# GateDriver.net
KiCad netlist of a schematic drawn in Altium Designer
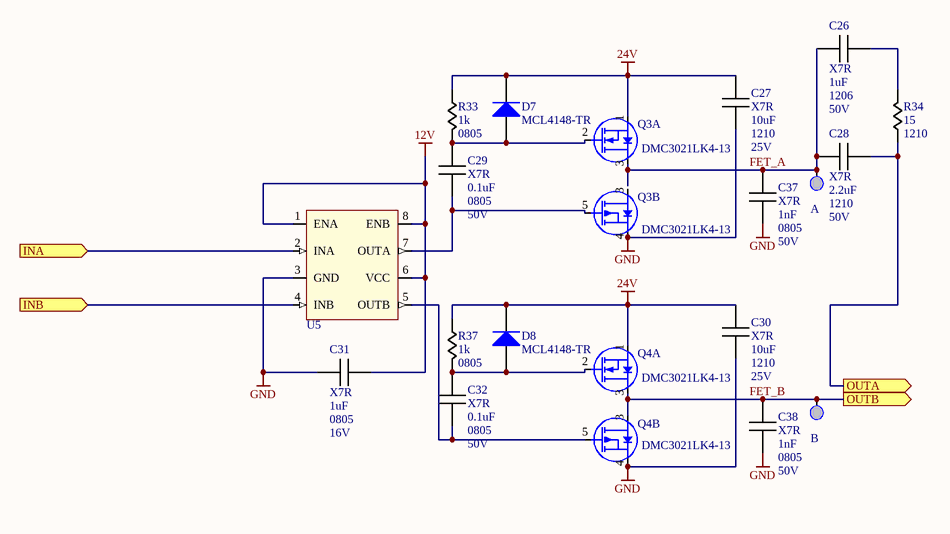
[diagram p0: GateDriver.SchDoc]

(export (version "E")
  (design (tool "Eeschema 10.0.6"))
  (components
    (comp (ref "A")
      (value "Testpoint")
      (footprint "Keystone5002")
      (fields (field (name "DIGIKEY PART") "36-5002-ND") (field (name "MOUSER PART") "534-5002"))
      (libsource (lib "UD2 CPLD") (part "Testpoint"))
    )
    (comp (ref "B")
      (value "Testpoint")
      (footprint "Keystone5002")
      (fields (field (name "DIGIKEY PART") "36-5002-ND") (field (name "MOUSER PART") "534-5002"))
      (libsource (lib "UD2 CPLD") (part "Testpoint"))
    )
    (comp (ref "C26")
      (value "GRM31MR71H105KA88L")
      (footprint "1206C")
      (description "CAP CER 1UF 50V X7R 1206")
      (fields
        (field (name "TOLERANCE") "10%")
        (field (name "MATERIAL") "X7R")
        (field (name "CAPACITANCE") "1uF")
        (field (name "PACKAGE") "1206")
        (field (name "VOLTAGE") "50V")
        (field (name "MOUSER PART") "81-GRM31MR71H105KA88")
      )
      (libsource (lib "UD2 CPLD") (part "Capacitor"))
    )
    (comp (ref "C27")
      (value "885012209028")
      (footprint "1210C")
      (description "CAP CER 10UF 25V X7R 1210")
      (fields
        (field (name "MATERIAL") "X7R")
        (field (name "CAPACITANCE") "10uF")
        (field (name "PACKAGE") "1210")
        (field (name "VOLTAGE") "25V")
        (field (name "MOUSER PART") "710-885012207094")
        (field (name "DIGIKEY PART") "732-7729-1-ND")
      )
      (libsource (lib "UD2 CPLD") (part "Capacitor"))
    )
    (comp (ref "C28")
      (value "CGA6M3X7R1H225K200AB")
      (footprint "1210C")
      (description "CAP ALUM 100UF 20% 16V RADIAL")
      (fields
        (field (name "TOLERANCE") "10%")
        (field (name "MATERIAL") "X7R")
        (field (name "CAPACITANCE") "2.2uF")
        (field (name "PACKAGE") "1210")
        (field (name "VOLTAGE") "50V")
        (field (name "MOUSER PART") "810-CGA6M3X7R1H225K")
      )
      (libsource (lib "UD2 CPLD") (part "Capacitor"))
    )
    (comp (ref "C29")
      (value "08055C104JAT2A")
      (footprint "0805C")
      (description "CAP CER 0.1UF 50V X7R 0805")
      (fields
        (field (name "MATERIAL") "X7R")
        (field (name "CAPACITANCE") "0.1uF")
        (field (name "PACKAGE") "0805")
        (field (name "VOLTAGE") "50V")
        (field (name "MOUSER PART") "581-08055C104J")
        (field (name "DIGIKEY PART") "478-3352-1-ND")
      )
      (libsource (lib "UD2 CPLD") (part "Capacitor"))
    )
    (comp (ref "C30")
      (value "885012209028")
      (footprint "1210C")
      (description "CAP CER 10UF 25V X7R 1210")
      (fields
        (field (name "MATERIAL") "X7R")
        (field (name "CAPACITANCE") "10uF")
        (field (name "PACKAGE") "1210")
        (field (name "VOLTAGE") "25V")
        (field (name "MOUSER PART") "710-885012207094")
        (field (name "DIGIKEY PART") "732-7729-1-ND")
      )
      (libsource (lib "UD2 CPLD") (part "Capacitor"))
    )
    (comp (ref "C31")
      (value "CC0805KKX7R7BB105")
      (footprint "0805C")
      (description "CAP CER 1UF 16V X7R 0805")
      (fields
        (field (name "TOLERANCE") "10%")
        (field (name "MATERIAL") "X7R")
        (field (name "CAPACITANCE") "1uF")
        (field (name "PACKAGE") "0805")
        (field (name "VOLTAGE") "16V")
        (field (name "MOUSER PART") "603-CC805KKX7R7BB105")
      )
      (libsource (lib "UD2 CPLD") (part "Capacitor"))
    )
    (comp (ref "C32")
      (value "08055C104JAT2A")
      (footprint "0805C")
      (description "CAP CER 0.1UF 50V X7R 0805")
      (fields
        (field (name "MATERIAL") "X7R")
        (field (name "CAPACITANCE") "0.1uF")
        (field (name "PACKAGE") "0805")
        (field (name "VOLTAGE") "50V")
        (field (name "MOUSER PART") "581-08055C104J")
        (field (name "DIGIKEY PART") "478-3352-1-ND")
      )
      (libsource (lib "UD2 CPLD") (part "Capacitor"))
    )
    (comp (ref "C37")
      (value "C0805C102K5RACTU")
      (footprint "0805C")
      (description "CAP CER 1000PF 50V X7R 0805")
      (fields
        (field (name "MATERIAL") "X7R")
        (field (name "CAPACITANCE") "1nF")
        (field (name "PACKAGE") "0805")
        (field (name "VOLTAGE") "50V")
        (field (name "MOUSER PART") "80-C0805C102K5R")
        (field (name "DIGIKEY PART") "399-1147-1-ND")
      )
      (libsource (lib "UD2 CPLD") (part "Capacitor"))
    )
    (comp (ref "C38")
      (value "C0805C102K5RACTU")
      (footprint "0805C")
      (description "CAP CER 1000PF 50V X7R 0805")
      (fields
        (field (name "MATERIAL") "X7R")
        (field (name "CAPACITANCE") "1nF")
        (field (name "PACKAGE") "0805")
        (field (name "VOLTAGE") "50V")
        (field (name "MOUSER PART") "80-C0805C102K5R")
        (field (name "DIGIKEY PART") "399-1147-1-ND")
      )
      (libsource (lib "UD2 CPLD") (part "Capacitor"))
    )
    (comp (ref "D7")
      (value "MCL4148-TR")
      (footprint "MicroMELF")
      (description "DIODE GEN 75V 150MA MICROMELF")
      (fields (field (name "MOUSER PART") "78-MCL4148") (field (name "DIGIKEY PART") "MCL4148CT-ND"))
      (libsource (lib "UD2 CPLD") (part "1N4148"))
    )
    (comp (ref "D8")
      (value "MCL4148-TR")
      (footprint "MicroMELF")
      (description "DIODE GEN 75V 150MA MICROMELF")
      (fields (field (name "MOUSER PART") "78-MCL4148") (field (name "DIGIKEY PART") "MCL4148CT-ND"))
      (libsource (lib "UD2 CPLD") (part "1N4148"))
    )
    (comp (ref "Q3")
      (value "DMC3021LK4-13")
      (footprint "TO-252")
      (description "MOSFET N/P-CH 30V TO252-4L")
      (fields
        (field (name "MOUSER PART") "621-DMC3021LK4-13")
        (field (name "DIGIKEY PART") "DMC3021LK4-13DICT-ND")
      )
      (libsource (lib "UD2 CPLD") (part "FDD8424H"))
    )
    (comp (ref "Q4")
      (value "DMC3021LK4-13")
      (footprint "TO-252")
      (description "MOSFET N/P-CH 30V TO252-4L")
      (fields
        (field (name "MOUSER PART") "621-DMC3021LK4-13")
        (field (name "DIGIKEY PART") "DMC3021LK4-13DICT-ND")
      )
      (libsource (lib "UD2 CPLD") (part "FDD8424H"))
    )
    (comp (ref "R33")
      (value "RC0805FR-071KL")
      (footprint "0805R")
      (description "RES SMD 1K OHM 1% 1/8W 0805")
      (fields
        (field (name "POWER") "0.125W")
        (field (name "RESISTANCE") "1k")
        (field (name "PACKAGE") "0805")
        (field (name "TOLERANCE") "1%")
      )
      (libsource (lib "UD2 CPLD") (part "Resistor"))
    )
    (comp (ref "R34")
      (value "CRCW121015R0JNEAHP")
      (footprint "1210R")
      (description "RES SMD 15 OHM 5% 3/4W 1210")
      (fields
        (field (name "RESISTANCE") "15")
        (field (name "PACKAGE") "1210")
        (field (name "POWER") "750mW")
        (field (name "TOLERANCE") "5%")
      )
      (libsource (lib "UD2 CPLD") (part "Resistor"))
    )
    (comp (ref "R37")
      (value "RC0805FR-071KL")
      (footprint "0805R")
      (description "RES SMD 1K OHM 1% 1/8W 0805")
      (fields
        (field (name "POWER") "0.125W")
        (field (name "RESISTANCE") "1k")
        (field (name "PACKAGE") "0805")
        (field (name "TOLERANCE") "1%")
      )
      (libsource (lib "UD2 CPLD") (part "Resistor"))
    )
    (comp (ref "U5")
      (value "MIC4126YME")
      (footprint "SOIC-8")
      (description "IC DRIVER MOSFET 1.5A DUAL 8SOIC")
      (fields (field (name "MOUSER PART") "998-MIC4126YME") (field (name "DIGIKEY PART") "576-1185-ND"))
      (libsource (lib "UD2 CPLD") (part "UCC27423D"))
    )
  )
  (nets
    (net (code "1") (name "/FET_A") (class "Default")
      (node (ref "A") (pin "1") (pinfunction "1_1") (pintype "passive"))
      (node (ref "C26") (pin "1") (pinfunction "1_1") (pintype "passive"))
      (node (ref "C28") (pin "1") (pinfunction "1_1") (pintype "passive"))
      (node (ref "C37") (pin "2") (pinfunction "2_2") (pintype "passive"))
      (node (ref "Q3") (pin "3") (pinfunction "D1/D2_3") (pintype "passive"))
    )
    (net (code "2") (name "/FET_B") (class "Default")
      (node (ref "B") (pin "1") (pinfunction "1_1") (pintype "passive"))
      (node (ref "C38") (pin "2") (pinfunction "2_2") (pintype "passive"))
      (node (ref "Q4") (pin "3") (pinfunction "D1/D2_3") (pintype "passive"))
    )
    (net (code "3") (name "/INA") (class "Default")
      (node (ref "U5") (pin "2") (pinfunction "INA_2") (pintype "input"))
    )
    (net (code "4") (name "/INB") (class "Default")
      (node (ref "U5") (pin "4") (pinfunction "INB_4") (pintype "input"))
    )
    (net (code "5") (name "/OUTA") (class "Default")
      (node (ref "C28") (pin "2") (pinfunction "2_2") (pintype "passive"))
      (node (ref "R34") (pin "2") (pinfunction "2_2") (pintype "passive"))
    )
    (net (code "6") (name "12V") (class "Default")
      (node (ref "C31") (pin "2") (pinfunction "2_2") (pintype "passive"))
      (node (ref "U5") (pin "1") (pinfunction "ENA_1") (pintype "power_in"))
      (node (ref "U5") (pin "6") (pinfunction "VCC_6") (pintype "passive"))
      (node (ref "U5") (pin "8") (pinfunction "ENB_8") (pintype "passive"))
    )
    (net (code "7") (name "24V") (class "Default")
      (node (ref "C27") (pin "1") (pinfunction "1_1") (pintype "passive"))
      (node (ref "C30") (pin "1") (pinfunction "1_1") (pintype "passive"))
      (node (ref "D7") (pin "K") (pinfunction "K_K") (pintype "passive"))
      (node (ref "D8") (pin "K") (pinfunction "K_K") (pintype "passive"))
      (node (ref "Q3") (pin "1") (pinfunction "S1_1") (pintype "passive"))
      (node (ref "Q4") (pin "1") (pinfunction "S1_1") (pintype "passive"))
      (node (ref "R33") (pin "2") (pinfunction "2_2") (pintype "passive"))
      (node (ref "R37") (pin "2") (pinfunction "2_2") (pintype "passive"))
    )
    (net (code "8") (name "GND") (class "Default")
      (node (ref "C27") (pin "2") (pinfunction "2_2") (pintype "passive"))
      (node (ref "C30") (pin "2") (pinfunction "2_2") (pintype "passive"))
      (node (ref "C31") (pin "1") (pinfunction "1_1") (pintype "passive"))
      (node (ref "C37") (pin "1") (pinfunction "1_1") (pintype "passive"))
      (node (ref "C38") (pin "1") (pinfunction "1_1") (pintype "passive"))
      (node (ref "Q3") (pin "4") (pinfunction "S2_4") (pintype "passive"))
      (node (ref "Q4") (pin "4") (pinfunction "S2_4") (pintype "passive"))
      (node (ref "U5") (pin "3") (pinfunction "GND_3") (pintype "passive"))
    )
    (net (code "9") (name "Net-(C26-Pad2)") (class "Default")
      (node (ref "C26") (pin "2") (pinfunction "2_2") (pintype "passive"))
      (node (ref "R34") (pin "1") (pinfunction "1_1") (pintype "passive"))
    )
    (net (code "10") (name "Net-(Q3A-G1)") (class "Default")
      (node (ref "C29") (pin "2") (pinfunction "2_2") (pintype "passive"))
      (node (ref "D7") (pin "A") (pinfunction "A_A") (pintype "passive"))
      (node (ref "Q3") (pin "2") (pinfunction "G1_2") (pintype "passive"))
      (node (ref "R33") (pin "1") (pinfunction "1_1") (pintype "passive"))
    )
    (net (code "11") (name "Net-(Q3B-G2)") (class "Default")
      (node (ref "C29") (pin "1") (pinfunction "1_1") (pintype "passive"))
      (node (ref "Q3") (pin "5") (pinfunction "G2_5") (pintype "passive"))
      (node (ref "U5") (pin "7") (pinfunction "OUTA_7") (pintype "output"))
    )
    (net (code "12") (name "Net-(Q4A-G1)") (class "Default")
      (node (ref "C32") (pin "2") (pinfunction "2_2") (pintype "passive"))
      (node (ref "D8") (pin "A") (pinfunction "A_A") (pintype "passive"))
      (node (ref "Q4") (pin "2") (pinfunction "G1_2") (pintype "passive"))
      (node (ref "R37") (pin "1") (pinfunction "1_1") (pintype "passive"))
    )
    (net (code "13") (name "Net-(Q4B-G2)") (class "Default")
      (node (ref "C32") (pin "1") (pinfunction "1_1") (pintype "passive"))
      (node (ref "Q4") (pin "5") (pinfunction "G2_5") (pintype "passive"))
      (node (ref "U5") (pin "5") (pinfunction "OUTB_5") (pintype "output"))
    )
    (net (code "14") (name "unconnected-(Q3B-D1{slash}D2-Pad3)") (class "Default")
      (node (ref "Q3") (pin "3") (pinfunction "D1/D2_3") (pintype "passive"))
    )
  )
)
